# 2_4G8_1.net
KiCad netlist of a schematic drawn in EasyEDA Pro
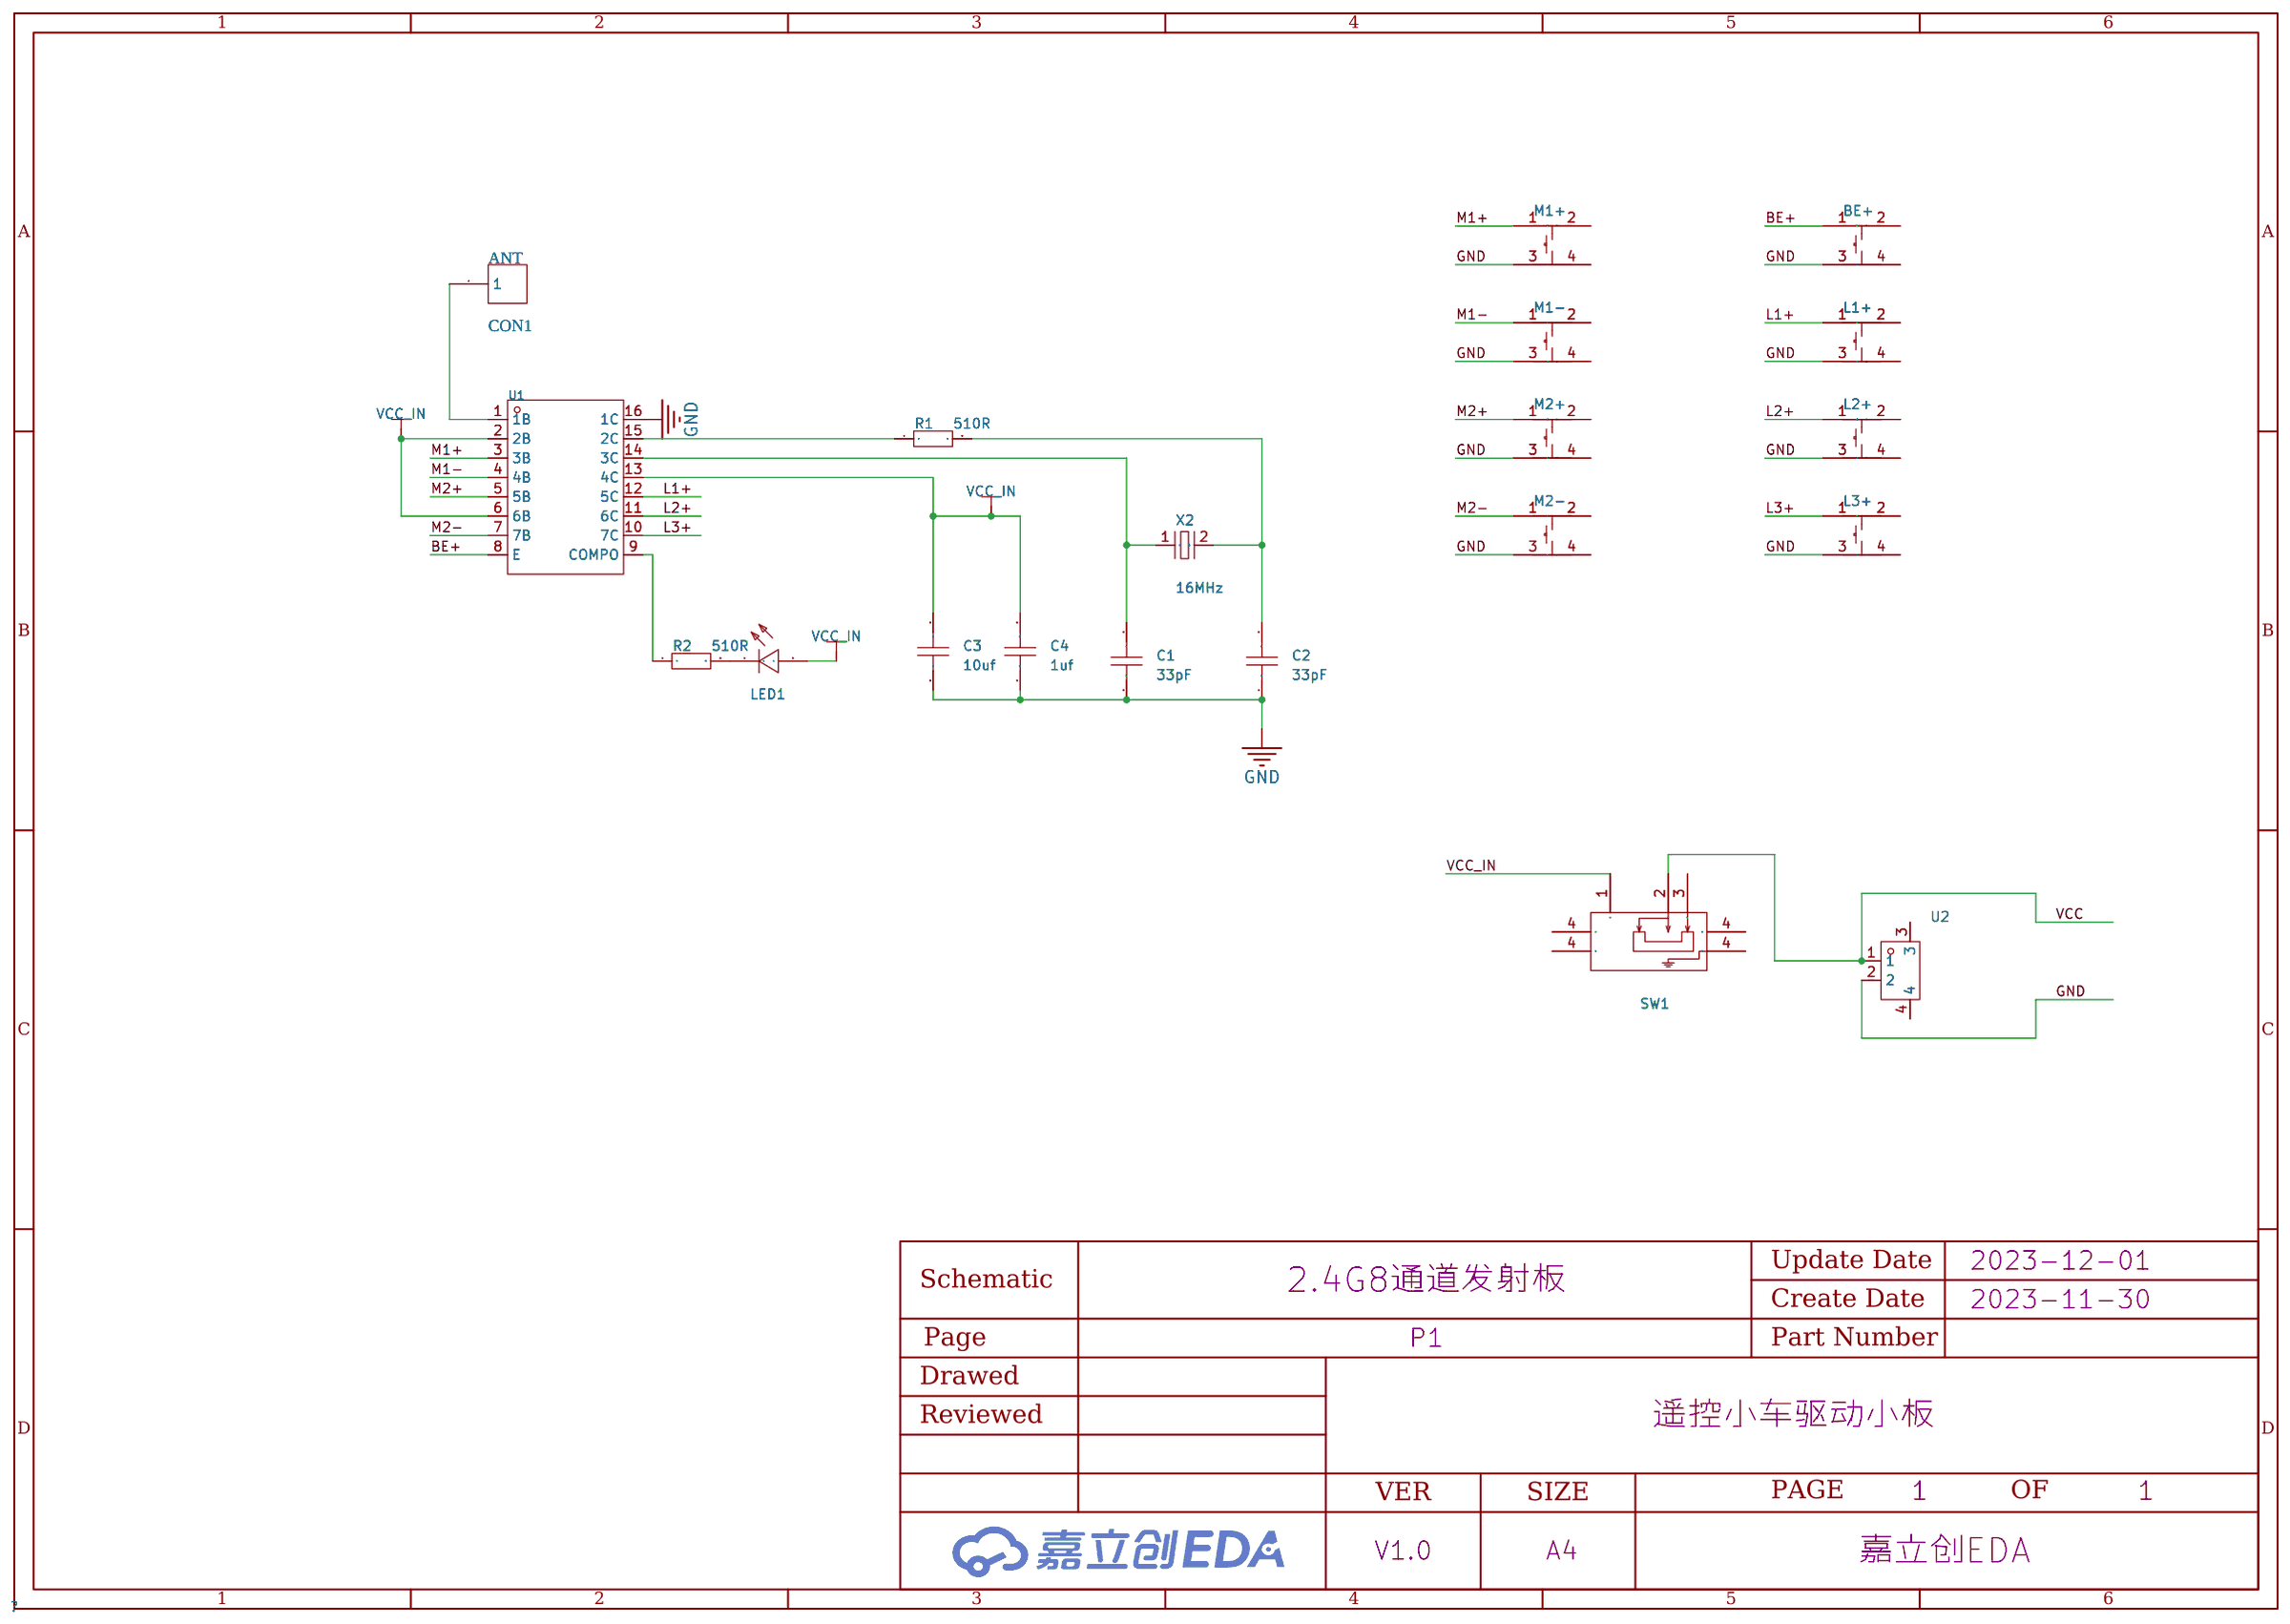
[diagram p0: schematic sheet]

(export (version "E")
  (design (tool "Eeschema 10.0.6"))
  (components
    (comp (ref "ANT")
      (value "CON1")
      (footprint "easyedapro:CON1_2")
      (libsource (lib "easyedapro") (part "CON1"))
    )
    (comp (ref "BE+")
      (value "TS-1095S-A1B3-C2D1")
      (footprint "easyedapro:SW-SMD_4P-L6.0-W6.0-P4.50-LS8.5")
      (description "电路结构:单刀单掷;按钮作用方向:顶部触动;致动器样式:圆形按钮;照明颜色:-;作用力:250gf ±30gf;开关长度:6mm;开关宽度:6mm;开关高度:4.3mm;")
      (fields (field (name "Manufacturer") "Yuandi(元迪)"))
      (libsource (lib "easyedapro") (part "TS-1095S-A1B3-C2D1"))
    )
    (comp (ref "C1")
      (value "33pF")
      (footprint "easyedapro:C0603")
      (libsource (lib "easyedapro") (part "CapAcitance"))
    )
    (comp (ref "C2")
      (value "33pF")
      (footprint "easyedapro:C0603")
      (libsource (lib "easyedapro") (part "CapAcitance"))
    )
    (comp (ref "C3")
      (value "10uf")
      (footprint "easyedapro:C0603")
      (libsource (lib "easyedapro") (part "CapAcitance"))
    )
    (comp (ref "C4")
      (value "1uf")
      (footprint "easyedapro:C0603")
      (libsource (lib "easyedapro") (part "CapAcitance"))
    )
    (comp (ref "L1+")
      (value "TS-1095S-A1B3-C2D1")
      (footprint "easyedapro:SW-SMD_4P-L6.0-W6.0-P4.50-LS8.5")
      (description "电路结构:单刀单掷;按钮作用方向:顶部触动;致动器样式:圆形按钮;照明颜色:-;作用力:250gf ±30gf;开关长度:6mm;开关宽度:6mm;开关高度:4.3mm;")
      (fields (field (name "Manufacturer") "Yuandi(元迪)"))
      (libsource (lib "easyedapro") (part "TS-1095S-A1B3-C2D1"))
    )
    (comp (ref "L2+")
      (value "TS-1095S-A1B3-C2D1")
      (footprint "easyedapro:SW-SMD_4P-L6.0-W6.0-P4.50-LS8.5")
      (description "电路结构:单刀单掷;按钮作用方向:顶部触动;致动器样式:圆形按钮;照明颜色:-;作用力:250gf ±30gf;开关长度:6mm;开关宽度:6mm;开关高度:4.3mm;")
      (fields (field (name "Manufacturer") "Yuandi(元迪)"))
      (libsource (lib "easyedapro") (part "TS-1095S-A1B3-C2D1"))
    )
    (comp (ref "L3+")
      (value "TS-1095S-A1B3-C2D1")
      (footprint "easyedapro:SW-SMD_4P-L6.0-W6.0-P4.50-LS8.5")
      (description "电路结构:单刀单掷;按钮作用方向:顶部触动;致动器样式:圆形按钮;照明颜色:-;作用力:250gf ±30gf;开关长度:6mm;开关宽度:6mm;开关高度:4.3mm;")
      (fields (field (name "Manufacturer") "Yuandi(元迪)"))
      (libsource (lib "easyedapro") (part "TS-1095S-A1B3-C2D1"))
    )
    (comp (ref "LED1")
      (value "NCD0603R1")
      (footprint "easyedapro:LED0603-RD_RED")
      (description "发光颜色:红色;功率:65mW;透镜颜色:无色透明;主波长:615nm~630nm;发光强度:80mcd~220mcd;发光角度:130°;工作温度:-30°C~+85°C;")
      (fields (field (name "Manufacturer") "国星光电"))
      (libsource (lib "easyedapro") (part "FC-DA1608HRK-620D"))
    )
    (comp (ref "M1+")
      (value "TS-1095S-A1B3-C2D1")
      (footprint "easyedapro:SW-SMD_4P-L6.0-W6.0-P4.50-LS8.5")
      (description "电路结构:单刀单掷;按钮作用方向:顶部触动;致动器样式:圆形按钮;照明颜色:-;作用力:250gf ±30gf;开关长度:6mm;开关宽度:6mm;开关高度:4.3mm;")
      (fields (field (name "Manufacturer") "Yuandi(元迪)"))
      (libsource (lib "easyedapro") (part "TS-1095S-A1B3-C2D1"))
    )
    (comp (ref "M1-")
      (value "TS-1095S-A1B3-C2D1")
      (footprint "easyedapro:SW-SMD_4P-L6.0-W6.0-P4.50-LS8.5")
      (description "电路结构:单刀单掷;按钮作用方向:顶部触动;致动器样式:圆形按钮;照明颜色:-;作用力:250gf ±30gf;开关长度:6mm;开关宽度:6mm;开关高度:4.3mm;")
      (fields (field (name "Manufacturer") "Yuandi(元迪)"))
      (libsource (lib "easyedapro") (part "TS-1095S-A1B3-C2D1"))
    )
    (comp (ref "M2+")
      (value "TS-1095S-A1B3-C2D1")
      (footprint "easyedapro:SW-SMD_4P-L6.0-W6.0-P4.50-LS8.5")
      (description "电路结构:单刀单掷;按钮作用方向:顶部触动;致动器样式:圆形按钮;照明颜色:-;作用力:250gf ±30gf;开关长度:6mm;开关宽度:6mm;开关高度:4.3mm;")
      (fields (field (name "Manufacturer") "Yuandi(元迪)"))
      (libsource (lib "easyedapro") (part "TS-1095S-A1B3-C2D1"))
    )
    (comp (ref "M2-")
      (value "TS-1095S-A1B3-C2D1")
      (footprint "easyedapro:SW-SMD_4P-L6.0-W6.0-P4.50-LS8.5")
      (description "电路结构:单刀单掷;按钮作用方向:顶部触动;致动器样式:圆形按钮;照明颜色:-;作用力:250gf ±30gf;开关长度:6mm;开关宽度:6mm;开关高度:4.3mm;")
      (fields (field (name "Manufacturer") "Yuandi(元迪)"))
      (libsource (lib "easyedapro") (part "TS-1095S-A1B3-C2D1"))
    )
    (comp (ref "R1") (value "510R") (footprint "easyedapro:R0603") (libsource (lib "easyedapro") (part "电阻")))
    (comp (ref "R2") (value "510R") (footprint "easyedapro:R0603") (libsource (lib "easyedapro") (part "电阻")))
    (comp (ref "SW1")
      (value "MSK12C02")
      (footprint "easyedapro:SW-TH_MSK12C02")
      (fields (field (name "Manufacturer") "SHOU HAN(首韩)"))
      (libsource (lib "easyedapro") (part "MSK12C02"))
    )
    (comp (ref "U1")
      (value "ULN2003A")
      (footprint "easyedapro:SOP-16_L10.0-W3.9-P1.27-LS6.0-BL")
      (description "开态输入电压(VI(on)@Vce,Ic):3V@2V,300mA;集射极饱和压降(VCE(sat)@Ii,Ic):900mV;开态输入电流(Ii@Vi):930uA@3.85V;")
      (fields (field (name "Manufacturer") "UMW(友台半导体)"))
      (libsource (lib "easyedapro") (part "ULN2003A_C482013"))
    )
    (comp (ref "U2")
      (value "XD-GH-2PWT")
      (footprint "easyedapro:CONN-SMD_GH-2PWT")
      (description "参考系列:GH;间距:1.25mm;插针结构:1x2P;排数:1;每排PIN数:2;公母:公型插针;安装方式:卧贴;额定电流:1A;触头镀层:锡;工作温度范围:-40°C~+105°C;")
      (fields (field (name "Manufacturer") "XUNDA(讯答)"))
      (libsource (lib "easyedapro") (part "XD-GH-2PWT"))
    )
    (comp (ref "X2")
      (value "16MHz")
      (footprint "easyedapro:CRYSTAL-TH_BD3.0-P1.10-D0.4")
      (description "频率:16MHz;频率公差:±20ppm;负载电容:20pF;")
      (fields (field (name "Manufacturer Part") "Q3816000ZWFAC") (field (name "Manufacturer") "JYJE(晶友嘉)"))
      (libsource (lib "easyedapro") (part "Q3816000ZWFAC"))
    )
  )
  (nets
    (net (code "1") (name "/BE+") (class "Default")
      (node (ref "BE+") (pin "1") (pinfunction "1_1") (pintype "input"))
      (node (ref "U1") (pin "8") (pinfunction "E_8") (pintype "input"))
    )
    (net (code "2") (name "/L1+") (class "Default")
      (node (ref "L1+") (pin "1") (pinfunction "1_1") (pintype "input"))
      (node (ref "U1") (pin "12") (pinfunction "5C_12") (pintype "input"))
    )
    (net (code "3") (name "/L2+") (class "Default")
      (node (ref "L2+") (pin "1") (pinfunction "1_1") (pintype "input"))
      (node (ref "U1") (pin "11") (pinfunction "6C_11") (pintype "input"))
    )
    (net (code "4") (name "/L3+") (class "Default")
      (node (ref "L3+") (pin "1") (pinfunction "1_1") (pintype "input"))
      (node (ref "U1") (pin "10") (pinfunction "7C_10") (pintype "input"))
    )
    (net (code "5") (name "/M1+") (class "Default")
      (node (ref "M1+") (pin "1") (pinfunction "1_1") (pintype "input"))
      (node (ref "U1") (pin "3") (pinfunction "3B_3") (pintype "input"))
    )
    (net (code "6") (name "/M1-") (class "Default")
      (node (ref "M1-") (pin "1") (pinfunction "1_1") (pintype "input"))
      (node (ref "U1") (pin "4") (pinfunction "4B_4") (pintype "input"))
    )
    (net (code "7") (name "/M2+") (class "Default")
      (node (ref "M2+") (pin "1") (pinfunction "1_1") (pintype "input"))
      (node (ref "U1") (pin "5") (pinfunction "5B_5") (pintype "input"))
    )
    (net (code "8") (name "/M2-") (class "Default")
      (node (ref "M2-") (pin "1") (pinfunction "1_1") (pintype "input"))
      (node (ref "U1") (pin "7") (pinfunction "7B_7") (pintype "input"))
    )
    (net (code "9") (name "/VCC") (class "Default")
      (node (ref "SW1") (pin "2") (pinfunction "2_2") (pintype "input"))
      (node (ref "U2") (pin "1") (pinfunction "1_1") (pintype "unspecified"))
    )
    (net (code "10") (name "GND") (class "Default")
      (node (ref "BE+") (pin "3") (pinfunction "3_3") (pintype "input"))
      (node (ref "C1") (pin "1") (pinfunction "1_1") (pintype "input"))
      (node (ref "C2") (pin "1") (pinfunction "1_1") (pintype "input"))
      (node (ref "C3") (pin "1") (pinfunction "1_1") (pintype "input"))
      (node (ref "C4") (pin "1") (pinfunction "1_1") (pintype "input"))
      (node (ref "L1+") (pin "3") (pinfunction "3_3") (pintype "input"))
      (node (ref "L2+") (pin "3") (pinfunction "3_3") (pintype "input"))
      (node (ref "L3+") (pin "3") (pinfunction "3_3") (pintype "input"))
      (node (ref "M1+") (pin "3") (pinfunction "3_3") (pintype "input"))
      (node (ref "M1-") (pin "3") (pinfunction "3_3") (pintype "input"))
      (node (ref "M2+") (pin "3") (pinfunction "3_3") (pintype "input"))
      (node (ref "M2-") (pin "3") (pinfunction "3_3") (pintype "input"))
      (node (ref "U1") (pin "16") (pinfunction "1C_16") (pintype "input"))
      (node (ref "U2") (pin "2") (pinfunction "2_2") (pintype "unspecified"))
    )
    (net (code "11") (name "Net-(LED1-K)") (class "Default")
      (node (ref "LED1") (pin "1") (pinfunction "K_1") (pintype "input"))
      (node (ref "R2") (pin "2") (pinfunction "2_2") (pintype "input"))
    )
    (net (code "12") (name "Net-(U1-1B)") (class "Default")
      (node (ref "ANT") (pin "1") (pinfunction "1_1") (pintype "input"))
      (node (ref "U1") (pin "1") (pinfunction "1B_1") (pintype "input"))
    )
    (net (code "13") (name "Net-(U1-2C)") (class "Default")
      (node (ref "R1") (pin "1") (pinfunction "1_1") (pintype "input"))
      (node (ref "U1") (pin "15") (pinfunction "2C_15") (pintype "input"))
    )
    (net (code "14") (name "Net-(U1-3C)") (class "Default")
      (node (ref "C1") (pin "2") (pinfunction "2_2") (pintype "input"))
      (node (ref "U1") (pin "14") (pinfunction "3C_14") (pintype "input"))
      (node (ref "X2") (pin "1") (pinfunction "1_1") (pintype "input"))
    )
    (net (code "15") (name "Net-(U1-COMPO)") (class "Default")
      (node (ref "R2") (pin "1") (pinfunction "1_1") (pintype "input"))
      (node (ref "U1") (pin "9") (pinfunction "COMPO_9") (pintype "input"))
    )
    (net (code "16") (name "Net-(X2-GND)") (class "Default")
      (node (ref "C2") (pin "2") (pinfunction "2_2") (pintype "input"))
      (node (ref "R1") (pin "2") (pinfunction "2_2") (pintype "input"))
      (node (ref "X2") (pin "2") (pinfunction "GND_2") (pintype "input"))
    )
    (net (code "17") (name "VCC_IN") (class "Default")
      (node (ref "C3") (pin "2") (pinfunction "2_2") (pintype "input"))
      (node (ref "C4") (pin "2") (pinfunction "2_2") (pintype "input"))
      (node (ref "LED1") (pin "2") (pinfunction "A_2") (pintype "input"))
      (node (ref "SW1") (pin "1") (pinfunction "1_1") (pintype "input"))
      (node (ref "U1") (pin "13") (pinfunction "4C_13") (pintype "input"))
      (node (ref "U1") (pin "2") (pinfunction "2B_2") (pintype "input"))
      (node (ref "U1") (pin "6") (pinfunction "6B_6") (pintype "input"))
    )
    (net (code "18") (name "unconnected-(BE+-Pad2)") (class "Default")
      (node (ref "BE+") (pin "2") (pinfunction "2_2") (pintype "input"))
    )
    (net (code "19") (name "unconnected-(BE+-Pad4)") (class "Default")
      (node (ref "BE+") (pin "4") (pinfunction "4_4") (pintype "input"))
    )
    (net (code "20") (name "unconnected-(L1+-Pad2)") (class "Default")
      (node (ref "L1+") (pin "2") (pinfunction "2_2") (pintype "input"))
    )
    (net (code "21") (name "unconnected-(L1+-Pad4)") (class "Default")
      (node (ref "L1+") (pin "4") (pinfunction "4_4") (pintype "input"))
    )
    (net (code "22") (name "unconnected-(L2+-Pad2)") (class "Default")
      (node (ref "L2+") (pin "2") (pinfunction "2_2") (pintype "input"))
    )
    (net (code "23") (name "unconnected-(L2+-Pad4)") (class "Default")
      (node (ref "L2+") (pin "4") (pinfunction "4_4") (pintype "input"))
    )
    (net (code "24") (name "unconnected-(L3+-Pad2)") (class "Default")
      (node (ref "L3+") (pin "2") (pinfunction "2_2") (pintype "input"))
    )
    (net (code "25") (name "unconnected-(L3+-Pad4)") (class "Default")
      (node (ref "L3+") (pin "4") (pinfunction "4_4") (pintype "input"))
    )
    (net (code "26") (name "unconnected-(M1+-Pad2)") (class "Default")
      (node (ref "M1+") (pin "2") (pinfunction "2_2") (pintype "input"))
    )
    (net (code "27") (name "unconnected-(M1+-Pad4)") (class "Default")
      (node (ref "M1+") (pin "4") (pinfunction "4_4") (pintype "input"))
    )
    (net (code "28") (name "unconnected-(M1--Pad2)") (class "Default")
      (node (ref "M1-") (pin "2") (pinfunction "2_2") (pintype "input"))
    )
    (net (code "29") (name "unconnected-(M1--Pad4)") (class "Default")
      (node (ref "M1-") (pin "4") (pinfunction "4_4") (pintype "input"))
    )
    (net (code "30") (name "unconnected-(M2+-Pad2)") (class "Default")
      (node (ref "M2+") (pin "2") (pinfunction "2_2") (pintype "input"))
    )
    (net (code "31") (name "unconnected-(M2+-Pad4)") (class "Default")
      (node (ref "M2+") (pin "4") (pinfunction "4_4") (pintype "input"))
    )
    (net (code "32") (name "unconnected-(M2--Pad2)") (class "Default")
      (node (ref "M2-") (pin "2") (pinfunction "2_2") (pintype "input"))
    )
    (net (code "33") (name "unconnected-(M2--Pad4)") (class "Default")
      (node (ref "M2-") (pin "4") (pinfunction "4_4") (pintype "input"))
    )
    (net (code "34") (name "unconnected-(SW1-Pad3)") (class "Default")
      (node (ref "SW1") (pin "3") (pinfunction "3_3") (pintype "input"))
    )
    (net (code "35") (name "unconnected-(SW1-Pad4)") (class "Default")
      (node (ref "SW1") (pin "4") (pinfunction "4_4") (pintype "input"))
    )
    (net (code "36") (name "unconnected-(SW1-Pad4)_1") (class "Default")
      (node (ref "SW1") (pin "4") (pinfunction "4_4") (pintype "input"))
    )
    (net (code "37") (name "unconnected-(SW1-Pad4)_2") (class "Default")
      (node (ref "SW1") (pin "4") (pinfunction "4_4") (pintype "input"))
    )
    (net (code "38") (name "unconnected-(SW1-Pad4)_3") (class "Default")
      (node (ref "SW1") (pin "4") (pinfunction "4_4") (pintype "input"))
    )
    (net (code "39") (name "unconnected-(U2-Pad3)") (class "Default")
      (node (ref "U2") (pin "3") (pinfunction "3_3") (pintype "unspecified"))
    )
    (net (code "40") (name "unconnected-(U2-Pad4)") (class "Default")
      (node (ref "U2") (pin "4") (pinfunction "4_4") (pintype "unspecified"))
    )
  )
)
